# Powerboard.net
KiCad netlist of a schematic drawn in EAGLE
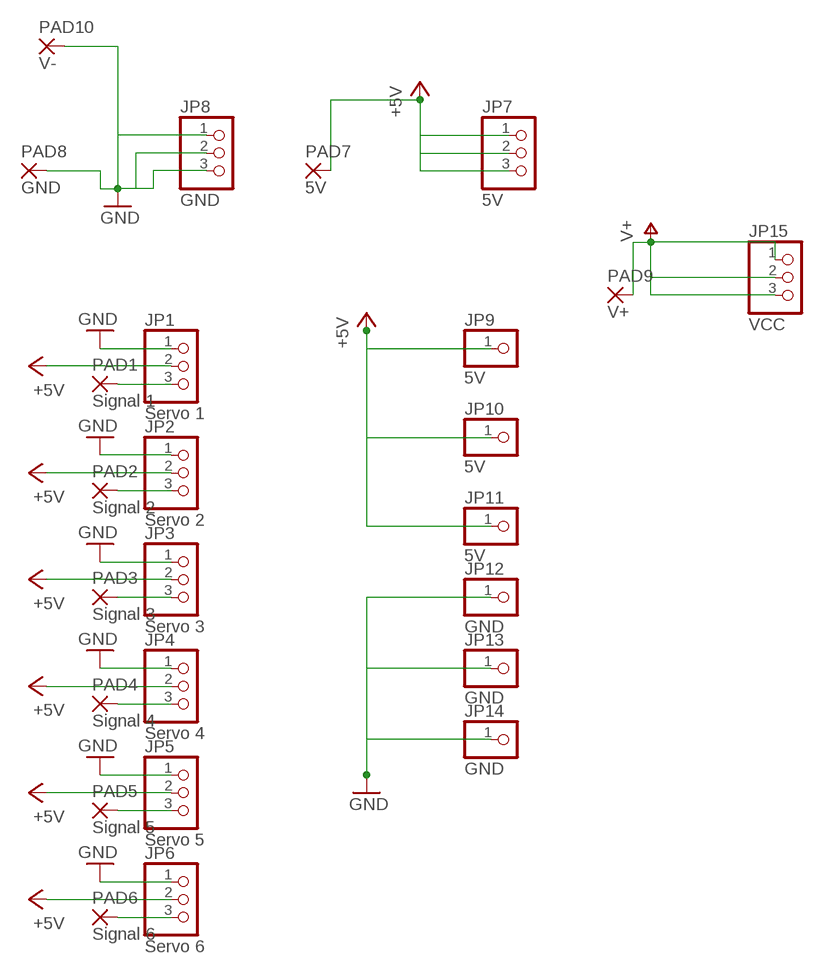
[diagram p0: schematic, sheet 1]

(export (version "E")
  (design (tool "Eeschema 10.0.6"))
  (components
    (comp (ref "JP1")
      (value "Servo 1")
      (footprint "eagle-import:1X03")
      (libsource (lib "eagle-import") (part "PINHD-1X3"))
    )
    (comp (ref "JP2")
      (value "Servo 2")
      (footprint "eagle-import:1X03")
      (libsource (lib "eagle-import") (part "PINHD-1X3"))
    )
    (comp (ref "JP3")
      (value "Servo 3")
      (footprint "eagle-import:1X03")
      (libsource (lib "eagle-import") (part "PINHD-1X3"))
    )
    (comp (ref "JP4")
      (value "Servo 4")
      (footprint "eagle-import:1X03")
      (libsource (lib "eagle-import") (part "PINHD-1X3"))
    )
    (comp (ref "JP5")
      (value "Servo 5")
      (footprint "eagle-import:1X03")
      (libsource (lib "eagle-import") (part "PINHD-1X3"))
    )
    (comp (ref "JP6")
      (value "Servo 6")
      (footprint "eagle-import:1X03")
      (libsource (lib "eagle-import") (part "PINHD-1X3"))
    )
    (comp (ref "JP7")
      (value "5V")
      (footprint "eagle-import:1X03")
      (libsource (lib "eagle-import") (part "PINHD-1X3"))
    )
    (comp (ref "JP8")
      (value "GND")
      (footprint "eagle-import:1X03")
      (libsource (lib "eagle-import") (part "PINHD-1X3"))
    )
    (comp (ref "JP9")
      (value "5V")
      (footprint "eagle-import:1X01")
      (libsource (lib "eagle-import") (part "PINHD-1X1"))
    )
    (comp (ref "JP10")
      (value "5V")
      (footprint "eagle-import:1X01")
      (libsource (lib "eagle-import") (part "PINHD-1X1"))
    )
    (comp (ref "JP11")
      (value "5V")
      (footprint "eagle-import:1X01")
      (libsource (lib "eagle-import") (part "PINHD-1X1"))
    )
    (comp (ref "JP12")
      (value "GND")
      (footprint "eagle-import:1X01")
      (libsource (lib "eagle-import") (part "PINHD-1X1"))
    )
    (comp (ref "JP13")
      (value "GND")
      (footprint "eagle-import:1X01")
      (libsource (lib "eagle-import") (part "PINHD-1X1"))
    )
    (comp (ref "JP14")
      (value "GND")
      (footprint "eagle-import:1X01")
      (libsource (lib "eagle-import") (part "PINHD-1X1"))
    )
    (comp (ref "JP15")
      (value "VCC")
      (footprint "eagle-import:1X03")
      (libsource (lib "eagle-import") (part "PINHD-1X3"))
    )
    (comp (ref "PAD1")
      (value "Signal 1")
      (footprint "eagle-import:3,81_1,4")
      (libsource (lib "eagle-import") (part "3,81/1,4"))
    )
    (comp (ref "PAD2")
      (value "Signal 2")
      (footprint "eagle-import:3,81_1,4")
      (libsource (lib "eagle-import") (part "3,81/1,4"))
    )
    (comp (ref "PAD3")
      (value "Signal 3")
      (footprint "eagle-import:3,81_1,4")
      (libsource (lib "eagle-import") (part "3,81/1,4"))
    )
    (comp (ref "PAD4")
      (value "Signal 4")
      (footprint "eagle-import:3,81_1,4")
      (libsource (lib "eagle-import") (part "3,81/1,4"))
    )
    (comp (ref "PAD5")
      (value "Signal 5")
      (footprint "eagle-import:3,81_1,4")
      (libsource (lib "eagle-import") (part "3,81/1,4"))
    )
    (comp (ref "PAD6")
      (value "Signal 6")
      (footprint "eagle-import:3,81_1,4")
      (libsource (lib "eagle-import") (part "3,81/1,4"))
    )
    (comp (ref "PAD7")
      (value "5V")
      (footprint "eagle-import:3,81_1,4")
      (libsource (lib "eagle-import") (part "3,81/1,4"))
    )
    (comp (ref "PAD8")
      (value "GND")
      (footprint "eagle-import:3,81_1,4")
      (libsource (lib "eagle-import") (part "3,81/1,4"))
    )
    (comp (ref "PAD9")
      (value "V+")
      (footprint "eagle-import:3,81_1,4")
      (libsource (lib "eagle-import") (part "3,81/1,4"))
    )
    (comp (ref "PAD10")
      (value "V-")
      (footprint "eagle-import:3,81_1,4")
      (libsource (lib "eagle-import") (part "3,81/1,4"))
    )
  )
  (nets
    (net (code "1") (name "+5V") (class "Default")
      (node (ref "JP1") (pin "2") (pinfunction "2_2") (pintype "passive"))
      (node (ref "JP10") (pin "1") (pinfunction "1_1") (pintype "passive"))
      (node (ref "JP11") (pin "1") (pinfunction "1_1") (pintype "passive"))
      (node (ref "JP2") (pin "2") (pinfunction "2_2") (pintype "passive"))
      (node (ref "JP3") (pin "2") (pinfunction "2_2") (pintype "passive"))
      (node (ref "JP4") (pin "2") (pinfunction "2_2") (pintype "passive"))
      (node (ref "JP5") (pin "2") (pinfunction "2_2") (pintype "passive"))
      (node (ref "JP6") (pin "2") (pinfunction "2_2") (pintype "passive"))
      (node (ref "JP7") (pin "1") (pinfunction "1_1") (pintype "passive"))
      (node (ref "JP7") (pin "2") (pinfunction "2_2") (pintype "passive"))
      (node (ref "JP7") (pin "3") (pinfunction "3_3") (pintype "passive"))
      (node (ref "JP9") (pin "1") (pinfunction "1_1") (pintype "passive"))
      (node (ref "PAD7") (pin "1") (pinfunction "P_1") (pintype "passive"))
    )
    (net (code "2") (name "GND") (class "Default")
      (node (ref "JP1") (pin "1") (pinfunction "1_1") (pintype "passive"))
      (node (ref "JP12") (pin "1") (pinfunction "1_1") (pintype "passive"))
      (node (ref "JP13") (pin "1") (pinfunction "1_1") (pintype "passive"))
      (node (ref "JP14") (pin "1") (pinfunction "1_1") (pintype "passive"))
      (node (ref "JP2") (pin "1") (pinfunction "1_1") (pintype "passive"))
      (node (ref "JP3") (pin "1") (pinfunction "1_1") (pintype "passive"))
      (node (ref "JP4") (pin "1") (pinfunction "1_1") (pintype "passive"))
      (node (ref "JP5") (pin "1") (pinfunction "1_1") (pintype "passive"))
      (node (ref "JP6") (pin "1") (pinfunction "1_1") (pintype "passive"))
      (node (ref "JP8") (pin "1") (pinfunction "1_1") (pintype "passive"))
      (node (ref "JP8") (pin "2") (pinfunction "2_2") (pintype "passive"))
      (node (ref "JP8") (pin "3") (pinfunction "3_3") (pintype "passive"))
      (node (ref "PAD10") (pin "1") (pinfunction "P_1") (pintype "passive"))
      (node (ref "PAD8") (pin "1") (pinfunction "P_1") (pintype "passive"))
    )
    (net (code "3") (name "Net-(PAD1-P)") (class "Default")
      (node (ref "JP1") (pin "3") (pinfunction "3_3") (pintype "passive"))
      (node (ref "PAD1") (pin "1") (pinfunction "P_1") (pintype "passive"))
    )
    (net (code "4") (name "Net-(PAD2-P)") (class "Default")
      (node (ref "JP2") (pin "3") (pinfunction "3_3") (pintype "passive"))
      (node (ref "PAD2") (pin "1") (pinfunction "P_1") (pintype "passive"))
    )
    (net (code "5") (name "Net-(PAD3-P)") (class "Default")
      (node (ref "JP3") (pin "3") (pinfunction "3_3") (pintype "passive"))
      (node (ref "PAD3") (pin "1") (pinfunction "P_1") (pintype "passive"))
    )
    (net (code "6") (name "Net-(PAD4-P)") (class "Default")
      (node (ref "JP4") (pin "3") (pinfunction "3_3") (pintype "passive"))
      (node (ref "PAD4") (pin "1") (pinfunction "P_1") (pintype "passive"))
    )
    (net (code "7") (name "Net-(PAD5-P)") (class "Default")
      (node (ref "JP5") (pin "3") (pinfunction "3_3") (pintype "passive"))
      (node (ref "PAD5") (pin "1") (pinfunction "P_1") (pintype "passive"))
    )
    (net (code "8") (name "Net-(PAD6-P)") (class "Default")
      (node (ref "JP6") (pin "3") (pinfunction "3_3") (pintype "passive"))
      (node (ref "PAD6") (pin "1") (pinfunction "P_1") (pintype "passive"))
    )
    (net (code "9") (name "V+") (class "Default")
      (node (ref "JP15") (pin "1") (pinfunction "1_1") (pintype "passive"))
      (node (ref "JP15") (pin "2") (pinfunction "2_2") (pintype "passive"))
      (node (ref "JP15") (pin "3") (pinfunction "3_3") (pintype "passive"))
      (node (ref "PAD9") (pin "1") (pinfunction "P_1") (pintype "passive"))
    )
  )
)
